# truco.net
KiCad netlist of a schematic drawn in EasyEDA
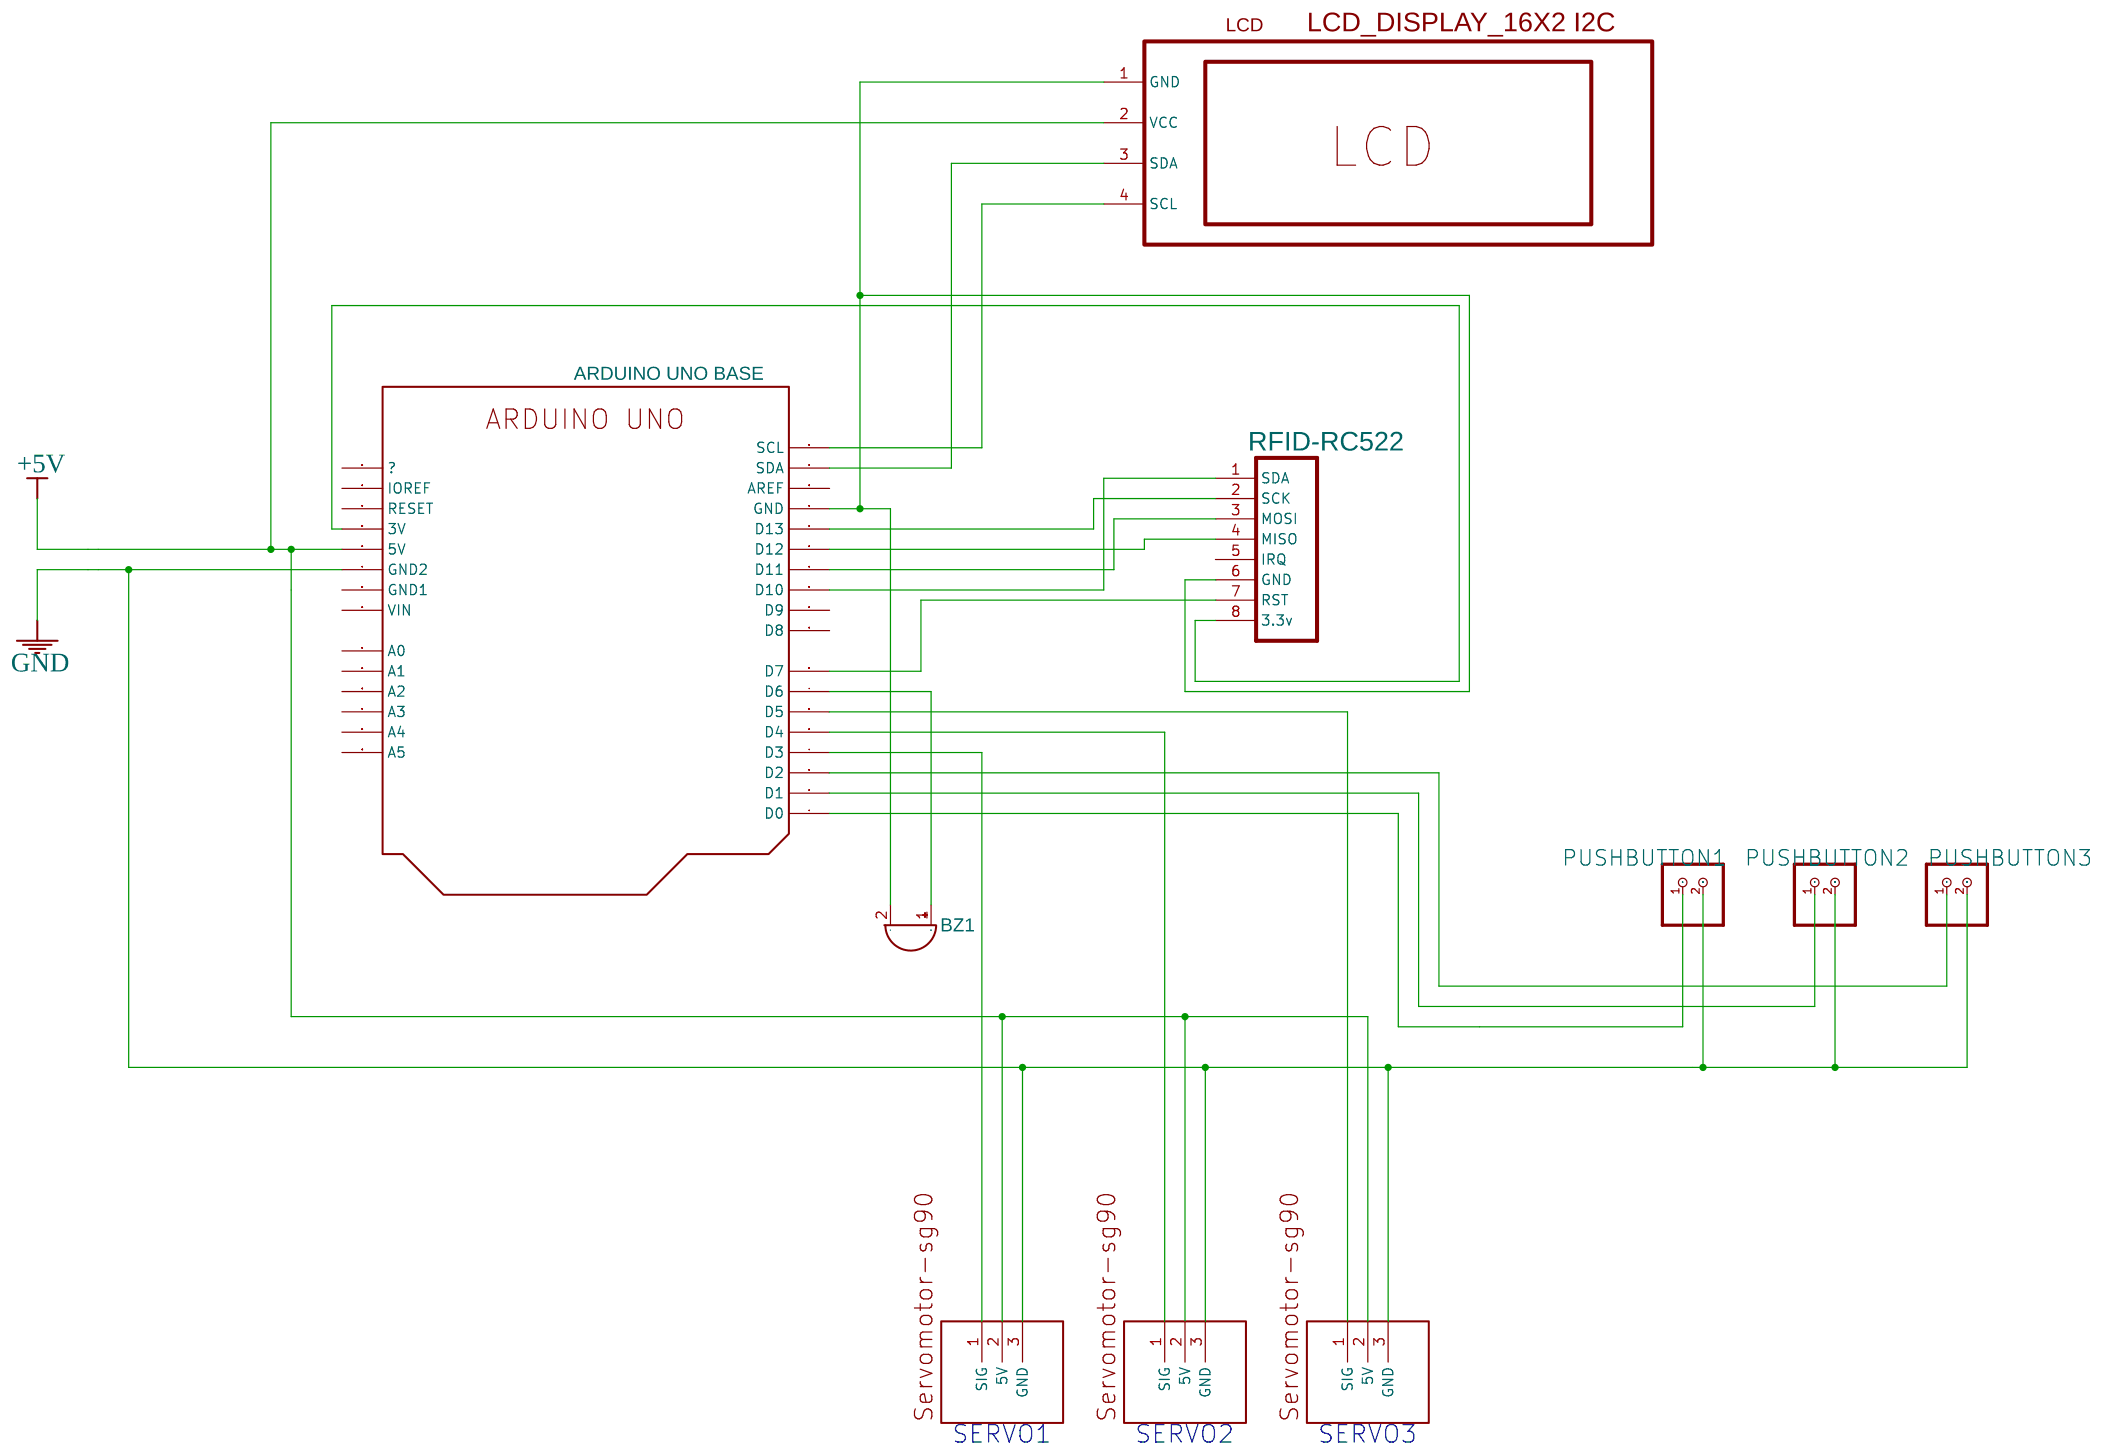
[diagram p0: schematic sheet]

(export (version "E")
  (design (tool "Eeschema 10.0.6"))
  (components
    (comp (ref "BZ1") (value "BUZZER 12X9.5 FATHBOARD") (libsource (lib "") (part "BUZZER 12X9.5 FATHBOARD")))
    (comp (ref "JP1") (value "RFID-RC522") (libsource (lib "") (part "RFID-RC522_2")))
    (comp (ref "PUSHBUTTON1") (value "PINHD-1X2") (libsource (lib "") (part "Unknown_865_-485")))
    (comp (ref "PUSHBUTTON2") (value "PINHD-1X2") (libsource (lib "") (part "Unknown_930_-485")))
    (comp (ref "PUSHBUTTON3") (value "PINHD-1X2") (libsource (lib "") (part "Unknown_995_-485")))
    (comp (ref "U1") (value "Servomotor sg90 - MG90S") (libsource (lib "") (part "Servomotor sg90 - MG90S")))
    (comp (ref "U2") (value "Servomotor sg90 - MG90S") (libsource (lib "") (part "Servomotor sg90 - MG90S")))
    (comp (ref "U3") (value "Servomotor sg90 - MG90S") (libsource (lib "") (part "Servomotor sg90 - MG90S")))
    (comp (ref "U5") (value "ARDUINO UNO BASE") (libsource (lib "") (part "ARDUINO UNO BASE")))
    (comp (ref "U7") (value "LCD 16x2 I2C Anschluss") (libsource (lib "") (part "LCD 16x2 I2C Anschluss")))
  )
  (nets
    (net (code "1") (name "+5V") (class "Default")
      (node (ref "U1") (pin "2") (pinfunction "5V_2") (pintype "unspecified"))
      (node (ref "U2") (pin "2") (pinfunction "5V_2") (pintype "unspecified"))
      (node (ref "U3") (pin "2") (pinfunction "5V_2") (pintype "unspecified"))
      (node (ref "U5") (pin "28") (pinfunction "5V_28") (pintype "passive"))
      (node (ref "U7") (pin "2") (pinfunction "VCC_2") (pintype "passive"))
    )
    (net (code "2") (name "GND") (class "Default")
      (node (ref "PUSHBUTTON1") (pin "2") (pinfunction "2_2") (pintype "bidirectional"))
      (node (ref "PUSHBUTTON2") (pin "2") (pinfunction "2_2") (pintype "bidirectional"))
      (node (ref "PUSHBUTTON3") (pin "2") (pinfunction "2_2") (pintype "bidirectional"))
      (node (ref "U1") (pin "3") (pinfunction "GND_3") (pintype "unspecified"))
      (node (ref "U2") (pin "3") (pinfunction "GND_3") (pintype "unspecified"))
      (node (ref "U3") (pin "3") (pinfunction "GND_3") (pintype "unspecified"))
      (node (ref "U5") (pin "27") (pinfunction "GND2_27") (pintype "passive"))
    )
    (net (code "3") (name "Net-(BZ1-+)") (class "Default")
      (node (ref "BZ1") (pin "1") (pinfunction "+_1") (pintype "unspecified"))
      (node (ref "U5") (pin "7") (pinfunction "D6_7") (pintype "unspecified"))
    )
    (net (code "4") (name "Net-(BZ1--)") (class "Default")
      (node (ref "BZ1") (pin "2") (pinfunction "-_2") (pintype "unspecified"))
      (node (ref "JP1") (pin "6") (pinfunction "GND_6") (pintype "unspecified"))
      (node (ref "U5") (pin "15") (pinfunction "GND_15") (pintype "passive"))
      (node (ref "U7") (pin "1") (pinfunction "GND_1") (pintype "passive"))
    )
    (net (code "5") (name "Net-(JP1-3.3v)") (class "Default")
      (node (ref "JP1") (pin "8") (pinfunction "3.3v_8") (pintype "passive"))
      (node (ref "U5") (pin "29") (pinfunction "3V_29") (pintype "passive"))
    )
    (net (code "6") (name "Net-(JP1-MISO)") (class "Default")
      (node (ref "JP1") (pin "4") (pinfunction "MISO_4") (pintype "output"))
      (node (ref "U5") (pin "13") (pinfunction "D12_13") (pintype "unspecified"))
    )
    (net (code "7") (name "Net-(JP1-MOSI)") (class "Default")
      (node (ref "JP1") (pin "3") (pinfunction "MOSI_3") (pintype "input"))
      (node (ref "U5") (pin "12") (pinfunction "D11_12") (pintype "unspecified"))
    )
    (net (code "8") (name "Net-(JP1-RST)") (class "Default")
      (node (ref "JP1") (pin "7") (pinfunction "RST_7") (pintype "input"))
      (node (ref "U5") (pin "8") (pinfunction "D7_8") (pintype "unspecified"))
    )
    (net (code "9") (name "Net-(JP1-SCK)") (class "Default")
      (node (ref "JP1") (pin "2") (pinfunction "SCK_2") (pintype "input"))
      (node (ref "U5") (pin "14") (pinfunction "D13_14") (pintype "unspecified"))
    )
    (net (code "10") (name "Net-(JP1-SDA)") (class "Default")
      (node (ref "JP1") (pin "1") (pinfunction "SDA_1") (pintype "input"))
      (node (ref "U5") (pin "11") (pinfunction "D10_11") (pintype "unspecified"))
    )
    (net (code "11") (name "Net-(U1-SIG)") (class "Default")
      (node (ref "U1") (pin "1") (pinfunction "SIG_1") (pintype "unspecified"))
      (node (ref "U5") (pin "4") (pinfunction "D3_4") (pintype "unspecified"))
    )
    (net (code "12") (name "Net-(U2-SIG)") (class "Default")
      (node (ref "U2") (pin "1") (pinfunction "SIG_1") (pintype "unspecified"))
      (node (ref "U5") (pin "5") (pinfunction "D4_5") (pintype "unspecified"))
    )
    (net (code "13") (name "Net-(U3-SIG)") (class "Default")
      (node (ref "U3") (pin "1") (pinfunction "SIG_1") (pintype "unspecified"))
      (node (ref "U5") (pin "6") (pinfunction "D5_6") (pintype "unspecified"))
    )
    (net (code "14") (name "Net-(U5-D0)") (class "Default")
      (node (ref "PUSHBUTTON1") (pin "1") (pinfunction "1_1") (pintype "bidirectional"))
      (node (ref "U5") (pin "1") (pinfunction "D0_1") (pintype "unspecified"))
    )
    (net (code "15") (name "Net-(U5-D1)") (class "Default")
      (node (ref "PUSHBUTTON2") (pin "1") (pinfunction "1_1") (pintype "bidirectional"))
      (node (ref "U5") (pin "2") (pinfunction "D1_2") (pintype "unspecified"))
    )
    (net (code "16") (name "Net-(U5-D2)") (class "Default")
      (node (ref "PUSHBUTTON3") (pin "1") (pinfunction "1_1") (pintype "bidirectional"))
      (node (ref "U5") (pin "3") (pinfunction "D2_3") (pintype "unspecified"))
    )
    (net (code "17") (name "Net-(U5-SCL)") (class "Default")
      (node (ref "U5") (pin "18") (pinfunction "SCL_18") (pintype "unspecified"))
      (node (ref "U7") (pin "4") (pinfunction "SCL_4") (pintype "passive"))
    )
    (net (code "18") (name "Net-(U5-SDA)") (class "Default")
      (node (ref "U5") (pin "17") (pinfunction "SDA_17") (pintype "unspecified"))
      (node (ref "U7") (pin "3") (pinfunction "SDA_3") (pintype "passive"))
    )
    (net (code "19") (name "unconnected-(JP1-IRQ-Pad5)") (class "Default")
      (node (ref "JP1") (pin "5") (pinfunction "IRQ_5") (pintype "output"))
    )
    (net (code "20") (name "unconnected-(U5-?-Pad32)") (class "Default")
      (node (ref "U5") (pin "32") (pinfunction "?_32") (pintype "unspecified"))
    )
    (net (code "21") (name "unconnected-(U5-A0-Pad24)") (class "Default")
      (node (ref "U5") (pin "24") (pinfunction "A0_24") (pintype "unspecified"))
    )
    (net (code "22") (name "unconnected-(U5-A1-Pad23)") (class "Default")
      (node (ref "U5") (pin "23") (pinfunction "A1_23") (pintype "unspecified"))
    )
    (net (code "23") (name "unconnected-(U5-A2-Pad22)") (class "Default")
      (node (ref "U5") (pin "22") (pinfunction "A2_22") (pintype "unspecified"))
    )
    (net (code "24") (name "unconnected-(U5-A3-Pad21)") (class "Default")
      (node (ref "U5") (pin "21") (pinfunction "A3_21") (pintype "unspecified"))
    )
    (net (code "25") (name "unconnected-(U5-A4-Pad20)") (class "Default")
      (node (ref "U5") (pin "20") (pinfunction "A4_20") (pintype "unspecified"))
    )
    (net (code "26") (name "unconnected-(U5-A5-Pad19)") (class "Default")
      (node (ref "U5") (pin "19") (pinfunction "A5_19") (pintype "unspecified"))
    )
    (net (code "27") (name "unconnected-(U5-AREF-Pad16)") (class "Default")
      (node (ref "U5") (pin "16") (pinfunction "AREF_16") (pintype "unspecified"))
    )
    (net (code "28") (name "unconnected-(U5-D8-Pad9)") (class "Default")
      (node (ref "U5") (pin "9") (pinfunction "D8_9") (pintype "unspecified"))
    )
    (net (code "29") (name "unconnected-(U5-D9-Pad10)") (class "Default")
      (node (ref "U5") (pin "10") (pinfunction "D9_10") (pintype "unspecified"))
    )
    (net (code "30") (name "unconnected-(U5-GND1-Pad26)") (class "Default")
      (node (ref "U5") (pin "26") (pinfunction "GND1_26") (pintype "passive"))
    )
    (net (code "31") (name "unconnected-(U5-IOREF-Pad31)") (class "Default")
      (node (ref "U5") (pin "31") (pinfunction "IOREF_31") (pintype "unspecified"))
    )
    (net (code "32") (name "unconnected-(U5-RESET-Pad30)") (class "Default")
      (node (ref "U5") (pin "30") (pinfunction "RESET_30") (pintype "unspecified"))
    )
    (net (code "33") (name "unconnected-(U5-VIN-Pad25)") (class "Default")
      (node (ref "U5") (pin "25") (pinfunction "VIN_25") (pintype "passive"))
    )
  )
)
